# untitled.net
KiCad netlist of a schematic drawn in EAGLE
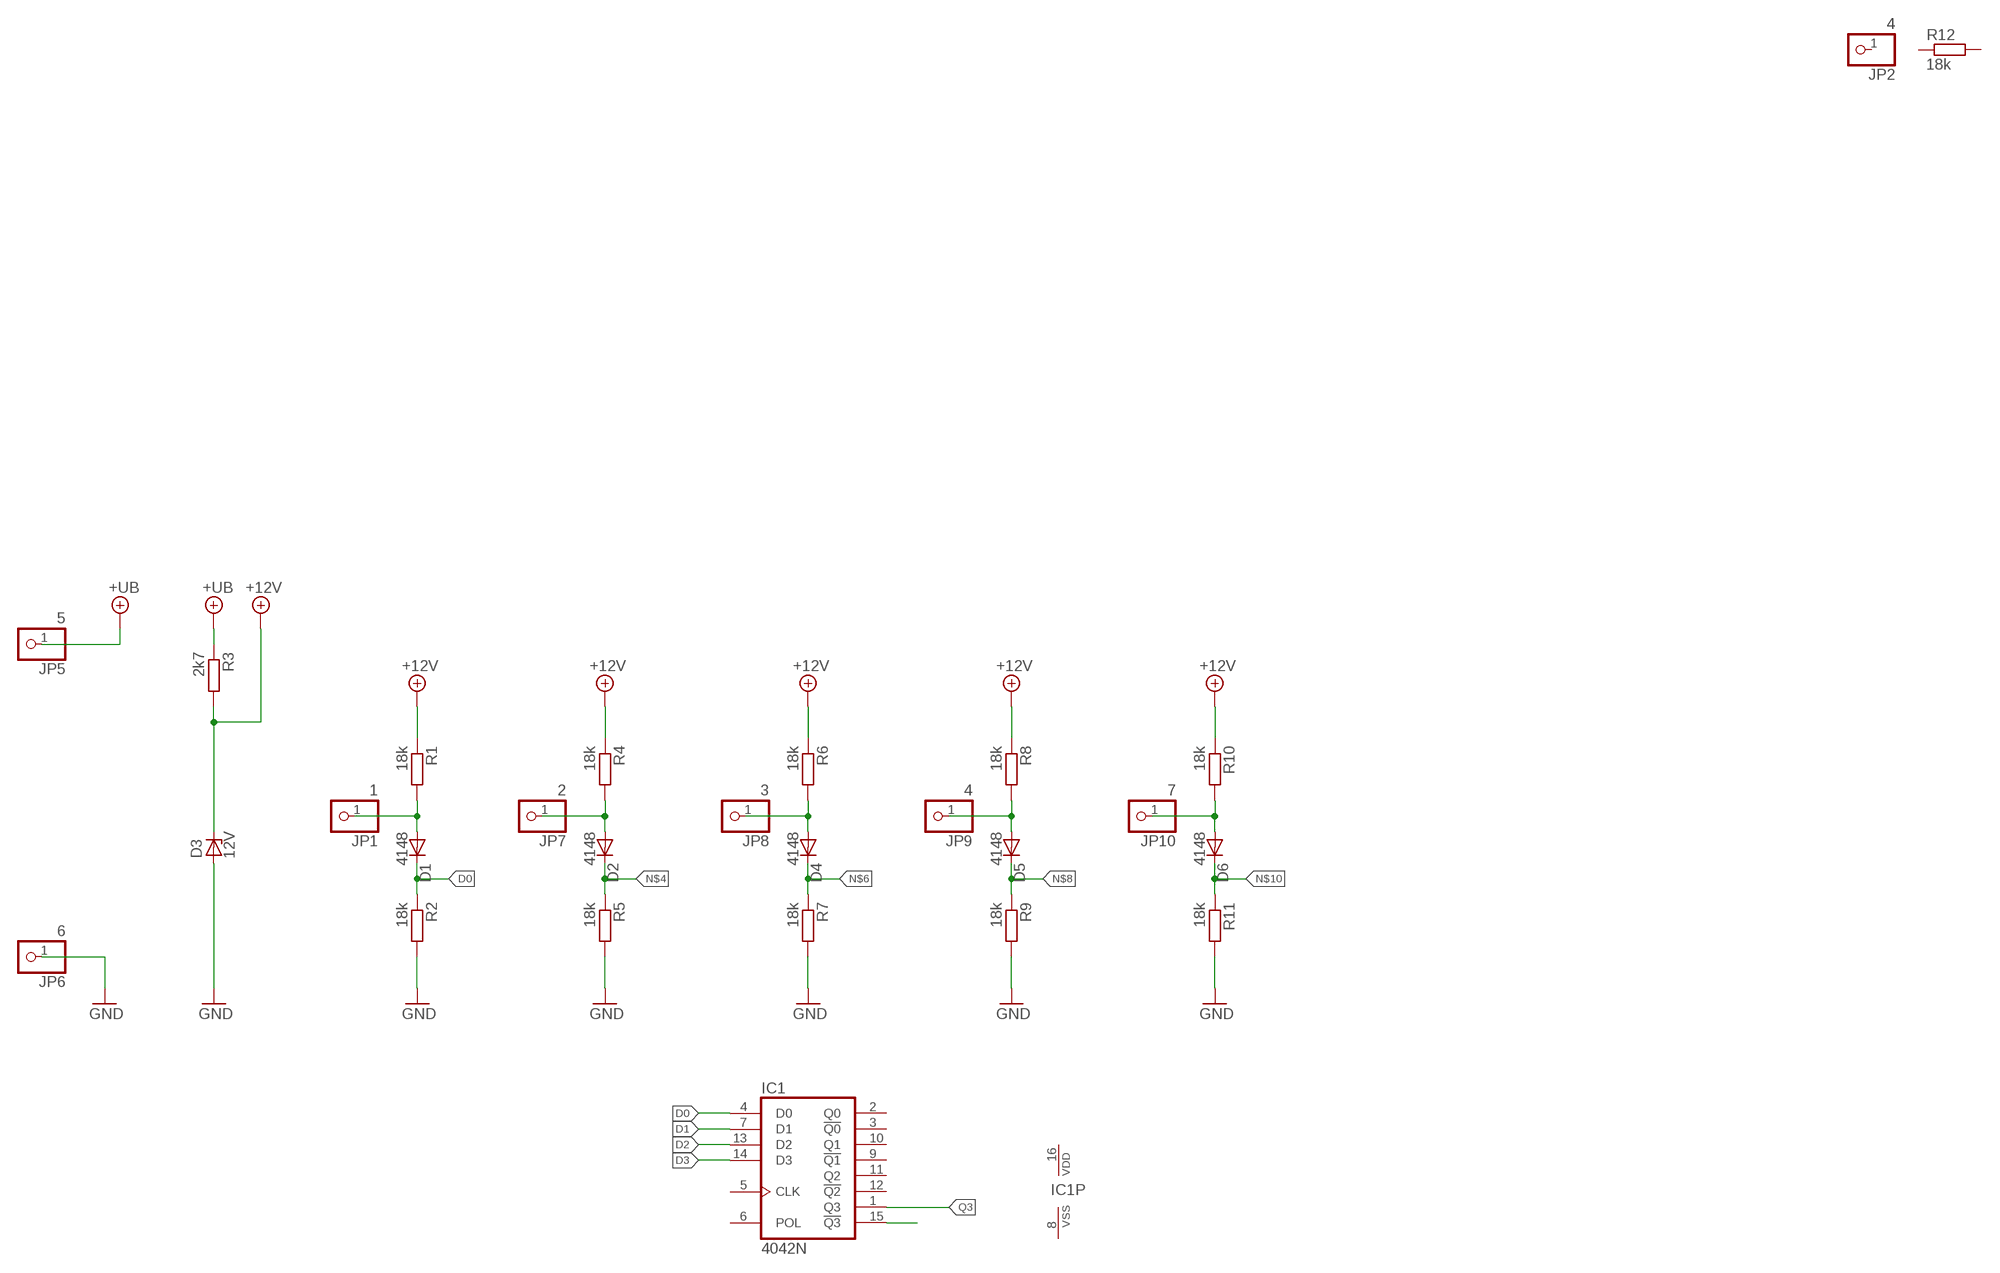
[diagram p0: schematic, sheet 1]

(export (version "E")
  (design (tool "Eeschema 10.0.6"))
  (components
    (comp (ref "D1")
      (value "4148")
      (footprint "eagle-import:DO35-7")
      (libsource (lib "eagle-import") (part "1N4148DO35-7"))
    )
    (comp (ref "D2")
      (value "4148")
      (footprint "eagle-import:DO35-7")
      (libsource (lib "eagle-import") (part "1N4148DO35-7"))
    )
    (comp (ref "D3")
      (value "12V")
      (footprint "eagle-import:DO34Z7")
      (libsource (lib "eagle-import") (part "BZV10"))
    )
    (comp (ref "D4")
      (value "4148")
      (footprint "eagle-import:DO35-7")
      (libsource (lib "eagle-import") (part "1N4148DO35-7"))
    )
    (comp (ref "D5")
      (value "4148")
      (footprint "eagle-import:DO35-7")
      (libsource (lib "eagle-import") (part "1N4148DO35-7"))
    )
    (comp (ref "D6")
      (value "4148")
      (footprint "eagle-import:DO35-7")
      (libsource (lib "eagle-import") (part "1N4148DO35-7"))
    )
    (comp (ref "IC1")
      (value "4042N")
      (footprint "eagle-import:DIL16")
      (libsource (lib "eagle-import") (part "4042N"))
    )
    (comp (ref "JP1")
      (value "1")
      (footprint "eagle-import:1X01")
      (libsource (lib "eagle-import") (part "PINHD-1X1"))
    )
    (comp (ref "JP2")
      (value "4")
      (footprint "eagle-import:1X01")
      (libsource (lib "eagle-import") (part "PINHD-1X1"))
    )
    (comp (ref "JP5")
      (value "5")
      (footprint "eagle-import:1X01")
      (libsource (lib "eagle-import") (part "PINHD-1X1"))
    )
    (comp (ref "JP6")
      (value "6")
      (footprint "eagle-import:1X01")
      (libsource (lib "eagle-import") (part "PINHD-1X1"))
    )
    (comp (ref "JP7")
      (value "2")
      (footprint "eagle-import:1X01")
      (libsource (lib "eagle-import") (part "PINHD-1X1"))
    )
    (comp (ref "JP8")
      (value "3")
      (footprint "eagle-import:1X01")
      (libsource (lib "eagle-import") (part "PINHD-1X1"))
    )
    (comp (ref "JP9")
      (value "4")
      (footprint "eagle-import:1X01")
      (libsource (lib "eagle-import") (part "PINHD-1X1"))
    )
    (comp (ref "JP10")
      (value "7")
      (footprint "eagle-import:1X01")
      (libsource (lib "eagle-import") (part "PINHD-1X1"))
    )
    (comp (ref "R1")
      (value "18k")
      (footprint "eagle-import:0207_7")
      (libsource (lib "eagle-import") (part "R-EU_0207/7"))
    )
    (comp (ref "R2")
      (value "18k")
      (footprint "eagle-import:0207_7")
      (libsource (lib "eagle-import") (part "R-EU_0207/7"))
    )
    (comp (ref "R3")
      (value "2k7")
      (footprint "eagle-import:0207_7")
      (libsource (lib "eagle-import") (part "R-EU_0207/7"))
    )
    (comp (ref "R4")
      (value "18k")
      (footprint "eagle-import:0207_7")
      (libsource (lib "eagle-import") (part "R-EU_0207/7"))
    )
    (comp (ref "R5")
      (value "18k")
      (footprint "eagle-import:0207_7")
      (libsource (lib "eagle-import") (part "R-EU_0207/7"))
    )
    (comp (ref "R6")
      (value "18k")
      (footprint "eagle-import:0207_7")
      (libsource (lib "eagle-import") (part "R-EU_0207/7"))
    )
    (comp (ref "R7")
      (value "18k")
      (footprint "eagle-import:0207_7")
      (libsource (lib "eagle-import") (part "R-EU_0207/7"))
    )
    (comp (ref "R8")
      (value "18k")
      (footprint "eagle-import:0207_7")
      (libsource (lib "eagle-import") (part "R-EU_0207/7"))
    )
    (comp (ref "R9")
      (value "18k")
      (footprint "eagle-import:0207_7")
      (libsource (lib "eagle-import") (part "R-EU_0207/7"))
    )
    (comp (ref "R10")
      (value "18k")
      (footprint "eagle-import:0207_7")
      (libsource (lib "eagle-import") (part "R-EU_0207/7"))
    )
    (comp (ref "R11")
      (value "18k")
      (footprint "eagle-import:0207_7")
      (libsource (lib "eagle-import") (part "R-EU_0207/7"))
    )
    (comp (ref "R12")
      (value "18k")
      (footprint "eagle-import:0207_7")
      (libsource (lib "eagle-import") (part "R-EU_0207/7"))
    )
  )
  (nets
    (net (code "1") (name "+12V") (class "Default")
      (node (ref "D3") (pin "C") (pinfunction "C_C") (pintype "passive"))
      (node (ref "R1") (pin "1") (pinfunction "1_1") (pintype "passive"))
      (node (ref "R10") (pin "1") (pinfunction "1_1") (pintype "passive"))
      (node (ref "R3") (pin "2") (pinfunction "2_2") (pintype "passive"))
      (node (ref "R4") (pin "1") (pinfunction "1_1") (pintype "passive"))
      (node (ref "R6") (pin "1") (pinfunction "1_1") (pintype "passive"))
      (node (ref "R8") (pin "1") (pinfunction "1_1") (pintype "passive"))
    )
    (net (code "2") (name "+UB") (class "Default")
      (node (ref "JP5") (pin "1") (pinfunction "1_1") (pintype "passive"))
      (node (ref "R3") (pin "1") (pinfunction "1_1") (pintype "passive"))
    )
    (net (code "3") (name "/VDD") (class "Default")
      (node (ref "IC1") (pin "16") (pinfunction "VDD_16") (pintype "power_in"))
    )
    (net (code "4") (name "/VSS") (class "Default")
      (node (ref "IC1") (pin "8") (pinfunction "VSS_8") (pintype "power_in"))
    )
    (net (code "5") (name "D0") (class "Default")
      (node (ref "D1") (pin "C") (pinfunction "C_C") (pintype "passive"))
      (node (ref "IC1") (pin "4") (pinfunction "D0_4") (pintype "input"))
      (node (ref "R2") (pin "1") (pinfunction "1_1") (pintype "passive"))
    )
    (net (code "6") (name "D1") (class "Default")
      (node (ref "IC1") (pin "7") (pinfunction "D1_7") (pintype "input"))
    )
    (net (code "7") (name "D2") (class "Default")
      (node (ref "IC1") (pin "13") (pinfunction "D2_13") (pintype "input"))
    )
    (net (code "8") (name "D3") (class "Default")
      (node (ref "IC1") (pin "14") (pinfunction "D3_14") (pintype "input"))
    )
    (net (code "9") (name "GND") (class "Default")
      (node (ref "D3") (pin "A") (pinfunction "A_A") (pintype "passive"))
      (node (ref "JP6") (pin "1") (pinfunction "1_1") (pintype "passive"))
      (node (ref "R11") (pin "2") (pinfunction "2_2") (pintype "passive"))
      (node (ref "R2") (pin "2") (pinfunction "2_2") (pintype "passive"))
      (node (ref "R5") (pin "2") (pinfunction "2_2") (pintype "passive"))
      (node (ref "R7") (pin "2") (pinfunction "2_2") (pintype "passive"))
      (node (ref "R9") (pin "2") (pinfunction "2_2") (pintype "passive"))
    )
    (net (code "10") (name "N$4") (class "Default")
      (node (ref "D2") (pin "C") (pinfunction "C_C") (pintype "passive"))
      (node (ref "R5") (pin "1") (pinfunction "1_1") (pintype "passive"))
    )
    (net (code "11") (name "N$6") (class "Default")
      (node (ref "D4") (pin "C") (pinfunction "C_C") (pintype "passive"))
      (node (ref "R7") (pin "1") (pinfunction "1_1") (pintype "passive"))
    )
    (net (code "12") (name "N$8") (class "Default")
      (node (ref "D5") (pin "C") (pinfunction "C_C") (pintype "passive"))
      (node (ref "R9") (pin "1") (pinfunction "1_1") (pintype "passive"))
    )
    (net (code "13") (name "N$10") (class "Default")
      (node (ref "D6") (pin "C") (pinfunction "C_C") (pintype "passive"))
      (node (ref "R11") (pin "1") (pinfunction "1_1") (pintype "passive"))
    )
    (net (code "14") (name "Net-(D1-PadA)") (class "Default")
      (node (ref "D1") (pin "A") (pinfunction "A_A") (pintype "passive"))
      (node (ref "JP1") (pin "1") (pinfunction "1_1") (pintype "passive"))
      (node (ref "R1") (pin "2") (pinfunction "2_2") (pintype "passive"))
    )
    (net (code "15") (name "Net-(D2-PadA)") (class "Default")
      (node (ref "D2") (pin "A") (pinfunction "A_A") (pintype "passive"))
      (node (ref "JP7") (pin "1") (pinfunction "1_1") (pintype "passive"))
      (node (ref "R4") (pin "2") (pinfunction "2_2") (pintype "passive"))
    )
    (net (code "16") (name "Net-(D4-PadA)") (class "Default")
      (node (ref "D4") (pin "A") (pinfunction "A_A") (pintype "passive"))
      (node (ref "JP8") (pin "1") (pinfunction "1_1") (pintype "passive"))
      (node (ref "R6") (pin "2") (pinfunction "2_2") (pintype "passive"))
    )
    (net (code "17") (name "Net-(D5-PadA)") (class "Default")
      (node (ref "D5") (pin "A") (pinfunction "A_A") (pintype "passive"))
      (node (ref "JP9") (pin "1") (pinfunction "1_1") (pintype "passive"))
      (node (ref "R8") (pin "2") (pinfunction "2_2") (pintype "passive"))
    )
    (net (code "18") (name "Net-(D6-PadA)") (class "Default")
      (node (ref "D6") (pin "A") (pinfunction "A_A") (pintype "passive"))
      (node (ref "JP10") (pin "1") (pinfunction "1_1") (pintype "passive"))
      (node (ref "R10") (pin "2") (pinfunction "2_2") (pintype "passive"))
    )
    (net (code "19") (name "Q3") (class "Default")
      (node (ref "IC1") (pin "1") (pinfunction "Q3_1") (pintype "output"))
    )
    (net (code "20") (name "unconnected-(IC1A-CLK-Pad5)") (class "Default")
      (node (ref "IC1") (pin "5") (pinfunction "CLK_5") (pintype "input"))
    )
    (net (code "21") (name "unconnected-(IC1A-POL-Pad6)") (class "Default")
      (node (ref "IC1") (pin "6") (pinfunction "POL_6") (pintype "input"))
    )
    (net (code "22") (name "unconnected-(IC1A-Q0-Pad2)") (class "Default")
      (node (ref "IC1") (pin "2") (pinfunction "Q0_2") (pintype "output"))
    )
    (net (code "23") (name "unconnected-(IC1A-Q1-Pad10)") (class "Default")
      (node (ref "IC1") (pin "10") (pinfunction "Q1_10") (pintype "output"))
    )
    (net (code "24") (name "unconnected-(IC1A-Q2-Pad11)") (class "Default")
      (node (ref "IC1") (pin "11") (pinfunction "Q2_11") (pintype "output"))
    )
    (net (code "25") (name "unconnected-(IC1A-~{Q0}-Pad3)") (class "Default")
      (node (ref "IC1") (pin "3") (pinfunction "~{Q0}_3") (pintype "output"))
    )
    (net (code "26") (name "unconnected-(IC1A-~{Q1}-Pad9)") (class "Default")
      (node (ref "IC1") (pin "9") (pinfunction "~{Q1}_9") (pintype "output"))
    )
    (net (code "27") (name "unconnected-(IC1A-~{Q2}-Pad12)") (class "Default")
      (node (ref "IC1") (pin "12") (pinfunction "~{Q2}_12") (pintype "output"))
    )
    (net (code "28") (name "unconnected-(IC1A-~{Q3}-Pad15)") (class "Default")
      (node (ref "IC1") (pin "15") (pinfunction "~{Q3}_15") (pintype "output"))
    )
    (net (code "29") (name "unconnected-(JP2-Pad1)") (class "Default")
      (node (ref "JP2") (pin "1") (pinfunction "1_1") (pintype "passive"))
    )
    (net (code "30") (name "unconnected-(R12-Pad1)") (class "Default")
      (node (ref "R12") (pin "1") (pinfunction "1_1") (pintype "passive"))
    )
    (net (code "31") (name "unconnected-(R12-Pad2)") (class "Default")
      (node (ref "R12") (pin "2") (pinfunction "2_2") (pintype "passive"))
    )
  )
)
